# lamp.net
KiCad netlist of a schematic drawn in EAGLE
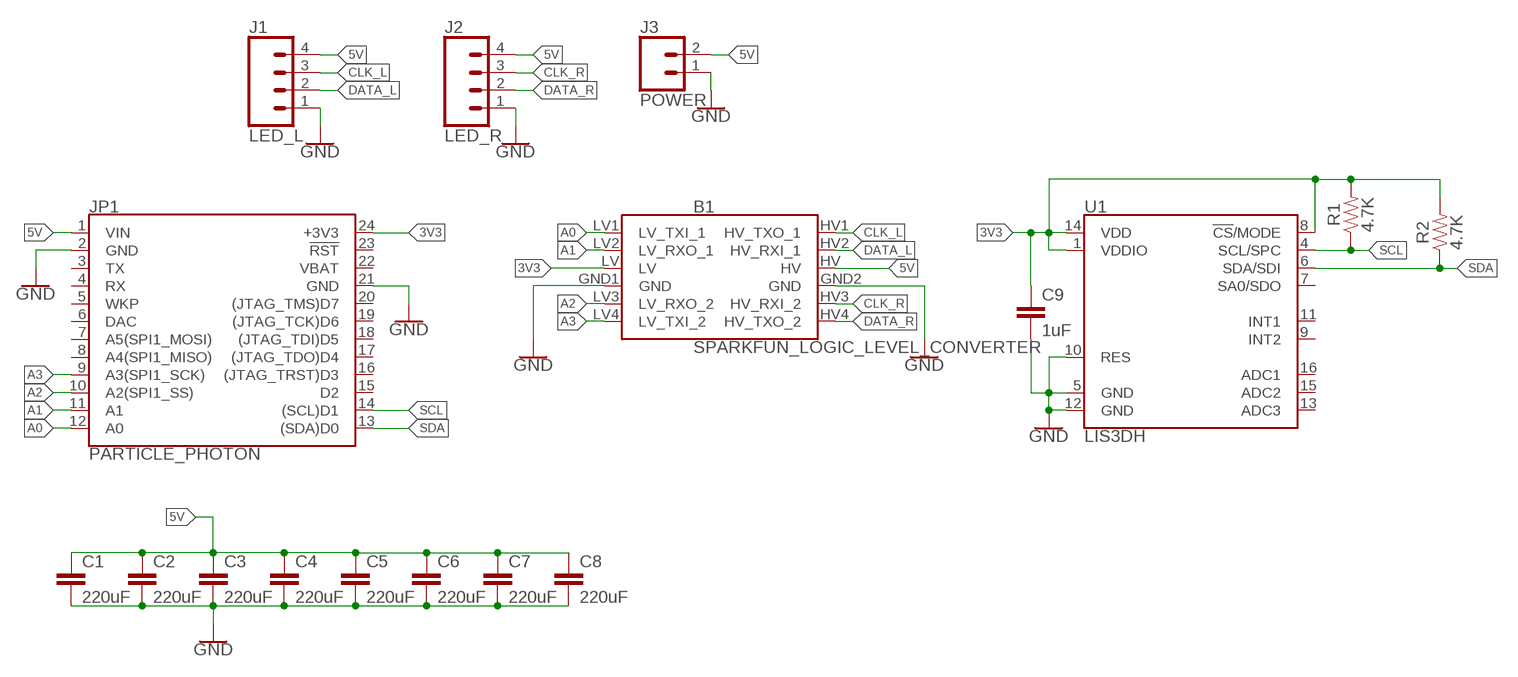
[diagram p0: schematic, sheet 1]

(export (version "E")
  (design (tool "Eeschema 10.0.6"))
  (components
    (comp (ref "B1")
      (value "SPARKFUN_LOGIC_LEVEL_CONVERTER")
      (footprint "eagle-import:SPARKFUN_LOGIC_LEVEL_CONVERTER")
      (libsource (lib "eagle-import") (part "SPARKFUN_LOGIC_LEVEL_CONVERTER"))
    )
    (comp (ref "C1")
      (value "220uF")
      (footprint "eagle-import:1206")
      (libsource (lib "eagle-import") (part "2.2UF-1206-50V-10%"))
    )
    (comp (ref "C2")
      (value "220uF")
      (footprint "eagle-import:1206")
      (libsource (lib "eagle-import") (part "2.2UF-1206-50V-10%"))
    )
    (comp (ref "C3")
      (value "220uF")
      (footprint "eagle-import:1206")
      (libsource (lib "eagle-import") (part "2.2UF-1206-50V-10%"))
    )
    (comp (ref "C4")
      (value "220uF")
      (footprint "eagle-import:1206")
      (libsource (lib "eagle-import") (part "2.2UF-1206-50V-10%"))
    )
    (comp (ref "C5")
      (value "220uF")
      (footprint "eagle-import:1206")
      (libsource (lib "eagle-import") (part "2.2UF-1206-50V-10%"))
    )
    (comp (ref "C6")
      (value "220uF")
      (footprint "eagle-import:1206")
      (libsource (lib "eagle-import") (part "2.2UF-1206-50V-10%"))
    )
    (comp (ref "C7")
      (value "220uF")
      (footprint "eagle-import:1206")
      (libsource (lib "eagle-import") (part "2.2UF-1206-50V-10%"))
    )
    (comp (ref "C8")
      (value "220uF")
      (footprint "eagle-import:1206")
      (libsource (lib "eagle-import") (part "2.2UF-1206-50V-10%"))
    )
    (comp (ref "C9")
      (value "1uF")
      (footprint "eagle-import:0603")
      (libsource (lib "eagle-import") (part "0.1UF-0603-25V-(+80/-20%)"))
    )
    (comp (ref "J1")
      (value "LED_L")
      (footprint "eagle-import:1X04_LONGPADS")
      (libsource (lib "eagle-import") (part "CONN_04LONGPADS"))
    )
    (comp (ref "J2")
      (value "LED_R")
      (footprint "eagle-import:1X04_LONGPADS")
      (libsource (lib "eagle-import") (part "CONN_04LONGPADS"))
    )
    (comp (ref "J3")
      (value "POWER")
      (footprint "eagle-import:1X02_LOCK_LONGPADS")
      (libsource (lib "eagle-import") (part "CONN_02LOCK_LONGPADS"))
    )
    (comp (ref "JP1")
      (value "PARTICLE_PHOTON")
      (footprint "eagle-import:PARTICLE_PHOTON")
      (libsource (lib "eagle-import") (part "PARTICLE_PHOTON"))
    )
    (comp (ref "R1")
      (value "4.7K")
      (footprint "eagle-import:0603")
      (libsource (lib "eagle-import") (part "0OHM-0603-1/10W-5%"))
    )
    (comp (ref "R2")
      (value "4.7K")
      (footprint "eagle-import:0603")
      (libsource (lib "eagle-import") (part "0OHM-0603-1/10W-5%"))
    )
    (comp (ref "U1")
      (value "LIS3DH")
      (footprint "eagle-import:LGA-16-3X3")
      (libsource (lib "eagle-import") (part "LIS3DH"))
    )
  )
  (nets
    (net (code "1") (name "/VBAT") (class "Default")
      (node (ref "JP1") (pin "22") (pinfunction "VBAT_22") (pintype "power_in"))
    )
    (net (code "2") (name "3V3") (class "Default")
      (node (ref "B1") (pin "LV") (pinfunction "LV_LV") (pintype "power_in"))
      (node (ref "C9") (pin "1") (pinfunction "1_1") (pintype "passive"))
      (node (ref "JP1") (pin "24") (pinfunction "+3V3_24") (pintype "power_in"))
      (node (ref "R1") (pin "2") (pinfunction "2_2") (pintype "passive"))
      (node (ref "R2") (pin "2") (pinfunction "2_2") (pintype "passive"))
      (node (ref "U1") (pin "1") (pinfunction "VDDIO_1") (pintype "bidirectional"))
      (node (ref "U1") (pin "14") (pinfunction "VDD_14") (pintype "bidirectional"))
      (node (ref "U1") (pin "8") (pinfunction "~{CS}/MODE_8") (pintype "bidirectional"))
    )
    (net (code "3") (name "5V") (class "Default")
      (node (ref "B1") (pin "HV") (pinfunction "HV_HV") (pintype "power_in"))
      (node (ref "C1") (pin "1") (pinfunction "1_1") (pintype "passive"))
      (node (ref "C2") (pin "1") (pinfunction "1_1") (pintype "passive"))
      (node (ref "C3") (pin "1") (pinfunction "1_1") (pintype "passive"))
      (node (ref "C4") (pin "1") (pinfunction "1_1") (pintype "passive"))
      (node (ref "C5") (pin "1") (pinfunction "1_1") (pintype "passive"))
      (node (ref "C6") (pin "1") (pinfunction "1_1") (pintype "passive"))
      (node (ref "C7") (pin "1") (pinfunction "1_1") (pintype "passive"))
      (node (ref "C8") (pin "1") (pinfunction "1_1") (pintype "passive"))
      (node (ref "J1") (pin "4") (pinfunction "4_4") (pintype "passive"))
      (node (ref "J2") (pin "4") (pinfunction "4_4") (pintype "passive"))
      (node (ref "J3") (pin "2") (pinfunction "2_2") (pintype "passive"))
      (node (ref "JP1") (pin "1") (pinfunction "VIN_1") (pintype "power_in"))
    )
    (net (code "4") (name "A0") (class "Default")
      (node (ref "B1") (pin "LV1") (pinfunction "LV_TXI_1_LV1") (pintype "bidirectional"))
      (node (ref "JP1") (pin "12") (pinfunction "A0_12") (pintype "bidirectional"))
    )
    (net (code "5") (name "A1") (class "Default")
      (node (ref "B1") (pin "LV2") (pinfunction "LV_RXO_1_LV2") (pintype "bidirectional"))
      (node (ref "JP1") (pin "11") (pinfunction "A1_11") (pintype "bidirectional"))
    )
    (net (code "6") (name "A2") (class "Default")
      (node (ref "B1") (pin "LV3") (pinfunction "LV_RXO_2_LV3") (pintype "bidirectional"))
      (node (ref "JP1") (pin "10") (pinfunction "A2(SPI1_SS)_10") (pintype "bidirectional"))
    )
    (net (code "7") (name "A3") (class "Default")
      (node (ref "B1") (pin "LV4") (pinfunction "LV_TXI_2_LV4") (pintype "bidirectional"))
      (node (ref "JP1") (pin "9") (pinfunction "A3(SPI1_SCK)_9") (pintype "bidirectional"))
    )
    (net (code "8") (name "CLK_L") (class "Default")
      (node (ref "B1") (pin "HV1") (pinfunction "HV_TXO_1_HV1") (pintype "bidirectional"))
      (node (ref "J1") (pin "3") (pinfunction "3_3") (pintype "passive"))
    )
    (net (code "9") (name "CLK_R") (class "Default")
      (node (ref "B1") (pin "HV3") (pinfunction "HV_RXI_2_HV3") (pintype "bidirectional"))
      (node (ref "J2") (pin "3") (pinfunction "3_3") (pintype "passive"))
    )
    (net (code "10") (name "DATA_L") (class "Default")
      (node (ref "B1") (pin "HV2") (pinfunction "HV_RXI_1_HV2") (pintype "bidirectional"))
      (node (ref "J1") (pin "2") (pinfunction "2_2") (pintype "passive"))
    )
    (net (code "11") (name "DATA_R") (class "Default")
      (node (ref "B1") (pin "HV4") (pinfunction "HV_TXO_2_HV4") (pintype "bidirectional"))
      (node (ref "J2") (pin "2") (pinfunction "2_2") (pintype "passive"))
    )
    (net (code "12") (name "GND") (class "Default")
      (node (ref "B1") (pin "GND1") (pinfunction "GND_GND1") (pintype "power_in"))
      (node (ref "B1") (pin "GND2") (pinfunction "GND_GND2") (pintype "power_in"))
      (node (ref "C1") (pin "2") (pinfunction "2_2") (pintype "passive"))
      (node (ref "C2") (pin "2") (pinfunction "2_2") (pintype "passive"))
      (node (ref "C3") (pin "2") (pinfunction "2_2") (pintype "passive"))
      (node (ref "C4") (pin "2") (pinfunction "2_2") (pintype "passive"))
      (node (ref "C5") (pin "2") (pinfunction "2_2") (pintype "passive"))
      (node (ref "C6") (pin "2") (pinfunction "2_2") (pintype "passive"))
      (node (ref "C7") (pin "2") (pinfunction "2_2") (pintype "passive"))
      (node (ref "C8") (pin "2") (pinfunction "2_2") (pintype "passive"))
      (node (ref "C9") (pin "2") (pinfunction "2_2") (pintype "passive"))
      (node (ref "J1") (pin "1") (pinfunction "1_1") (pintype "passive"))
      (node (ref "J2") (pin "1") (pinfunction "1_1") (pintype "passive"))
      (node (ref "J3") (pin "1") (pinfunction "1_1") (pintype "passive"))
      (node (ref "JP1") (pin "2") (pinfunction "GND_2") (pintype "power_in"))
      (node (ref "JP1") (pin "21") (pinfunction "GND_21") (pintype "power_in"))
      (node (ref "U1") (pin "10") (pinfunction "RES_10") (pintype "bidirectional"))
      (node (ref "U1") (pin "12") (pinfunction "GND_12") (pintype "bidirectional"))
      (node (ref "U1") (pin "5") (pinfunction "GND_5") (pintype "bidirectional"))
    )
    (net (code "13") (name "SCL") (class "Default")
      (node (ref "JP1") (pin "14") (pinfunction "(SCL)D1_14") (pintype "bidirectional"))
      (node (ref "R1") (pin "1") (pinfunction "1_1") (pintype "passive"))
      (node (ref "U1") (pin "4") (pinfunction "SCL/SPC_4") (pintype "bidirectional"))
    )
    (net (code "14") (name "SDA") (class "Default")
      (node (ref "JP1") (pin "13") (pinfunction "(SDA)D0_13") (pintype "bidirectional"))
      (node (ref "R2") (pin "1") (pinfunction "1_1") (pintype "passive"))
      (node (ref "U1") (pin "6") (pinfunction "SDA/SDI_6") (pintype "bidirectional"))
    )
    (net (code "15") (name "unconnected-(JP1-(JTAG_TCK)D6-Pad19)") (class "Default")
      (node (ref "JP1") (pin "19") (pinfunction "(JTAG_TCK)D6_19") (pintype "bidirectional"))
    )
    (net (code "16") (name "unconnected-(JP1-(JTAG_TDI)D5-Pad18)") (class "Default")
      (node (ref "JP1") (pin "18") (pinfunction "(JTAG_TDI)D5_18") (pintype "bidirectional"))
    )
    (net (code "17") (name "unconnected-(JP1-(JTAG_TDO)D4-Pad17)") (class "Default")
      (node (ref "JP1") (pin "17") (pinfunction "(JTAG_TDO)D4_17") (pintype "bidirectional"))
    )
    (net (code "18") (name "unconnected-(JP1-(JTAG_TMS)D7-Pad20)") (class "Default")
      (node (ref "JP1") (pin "20") (pinfunction "(JTAG_TMS)D7_20") (pintype "bidirectional"))
    )
    (net (code "19") (name "unconnected-(JP1-(JTAG_TRST)D3-Pad16)") (class "Default")
      (node (ref "JP1") (pin "16") (pinfunction "(JTAG_TRST)D3_16") (pintype "bidirectional"))
    )
    (net (code "20") (name "unconnected-(JP1-A4(SPI1_MISO)-Pad8)") (class "Default")
      (node (ref "JP1") (pin "8") (pinfunction "A4(SPI1_MISO)_8") (pintype "bidirectional"))
    )
    (net (code "21") (name "unconnected-(JP1-A5(SPI1_MOSI)-Pad7)") (class "Default")
      (node (ref "JP1") (pin "7") (pinfunction "A5(SPI1_MOSI)_7") (pintype "bidirectional"))
    )
    (net (code "22") (name "unconnected-(JP1-D2-Pad15)") (class "Default")
      (node (ref "JP1") (pin "15") (pinfunction "D2_15") (pintype "bidirectional"))
    )
    (net (code "23") (name "unconnected-(JP1-DAC-Pad6)") (class "Default")
      (node (ref "JP1") (pin "6") (pinfunction "DAC_6") (pintype "bidirectional"))
    )
    (net (code "24") (name "unconnected-(JP1-RX-Pad4)") (class "Default")
      (node (ref "JP1") (pin "4") (pinfunction "RX_4") (pintype "bidirectional"))
    )
    (net (code "25") (name "unconnected-(JP1-TX-Pad3)") (class "Default")
      (node (ref "JP1") (pin "3") (pinfunction "TX_3") (pintype "bidirectional"))
    )
    (net (code "26") (name "unconnected-(JP1-WKP-Pad5)") (class "Default")
      (node (ref "JP1") (pin "5") (pinfunction "WKP_5") (pintype "bidirectional"))
    )
    (net (code "27") (name "unconnected-(JP1-~{RST}-Pad23)") (class "Default")
      (node (ref "JP1") (pin "23") (pinfunction "~{RST}_23") (pintype "bidirectional"))
    )
    (net (code "28") (name "unconnected-(U1-ADC1-Pad16)") (class "Default")
      (node (ref "U1") (pin "16") (pinfunction "ADC1_16") (pintype "bidirectional"))
    )
    (net (code "29") (name "unconnected-(U1-ADC2-Pad15)") (class "Default")
      (node (ref "U1") (pin "15") (pinfunction "ADC2_15") (pintype "bidirectional"))
    )
    (net (code "30") (name "unconnected-(U1-ADC3-Pad13)") (class "Default")
      (node (ref "U1") (pin "13") (pinfunction "ADC3_13") (pintype "bidirectional"))
    )
    (net (code "31") (name "unconnected-(U1-INT1-Pad11)") (class "Default")
      (node (ref "U1") (pin "11") (pinfunction "INT1_11") (pintype "bidirectional"))
    )
    (net (code "32") (name "unconnected-(U1-INT2-Pad9)") (class "Default")
      (node (ref "U1") (pin "9") (pinfunction "INT2_9") (pintype "bidirectional"))
    )
    (net (code "33") (name "unconnected-(U1-SA0{slash}SDO-Pad7)") (class "Default")
      (node (ref "U1") (pin "7") (pinfunction "SA0/SDO_7") (pintype "bidirectional"))
    )
  )
)
